# LP_ECG_Main-X01.net
KiCad netlist of a schematic drawn in Altium Designer
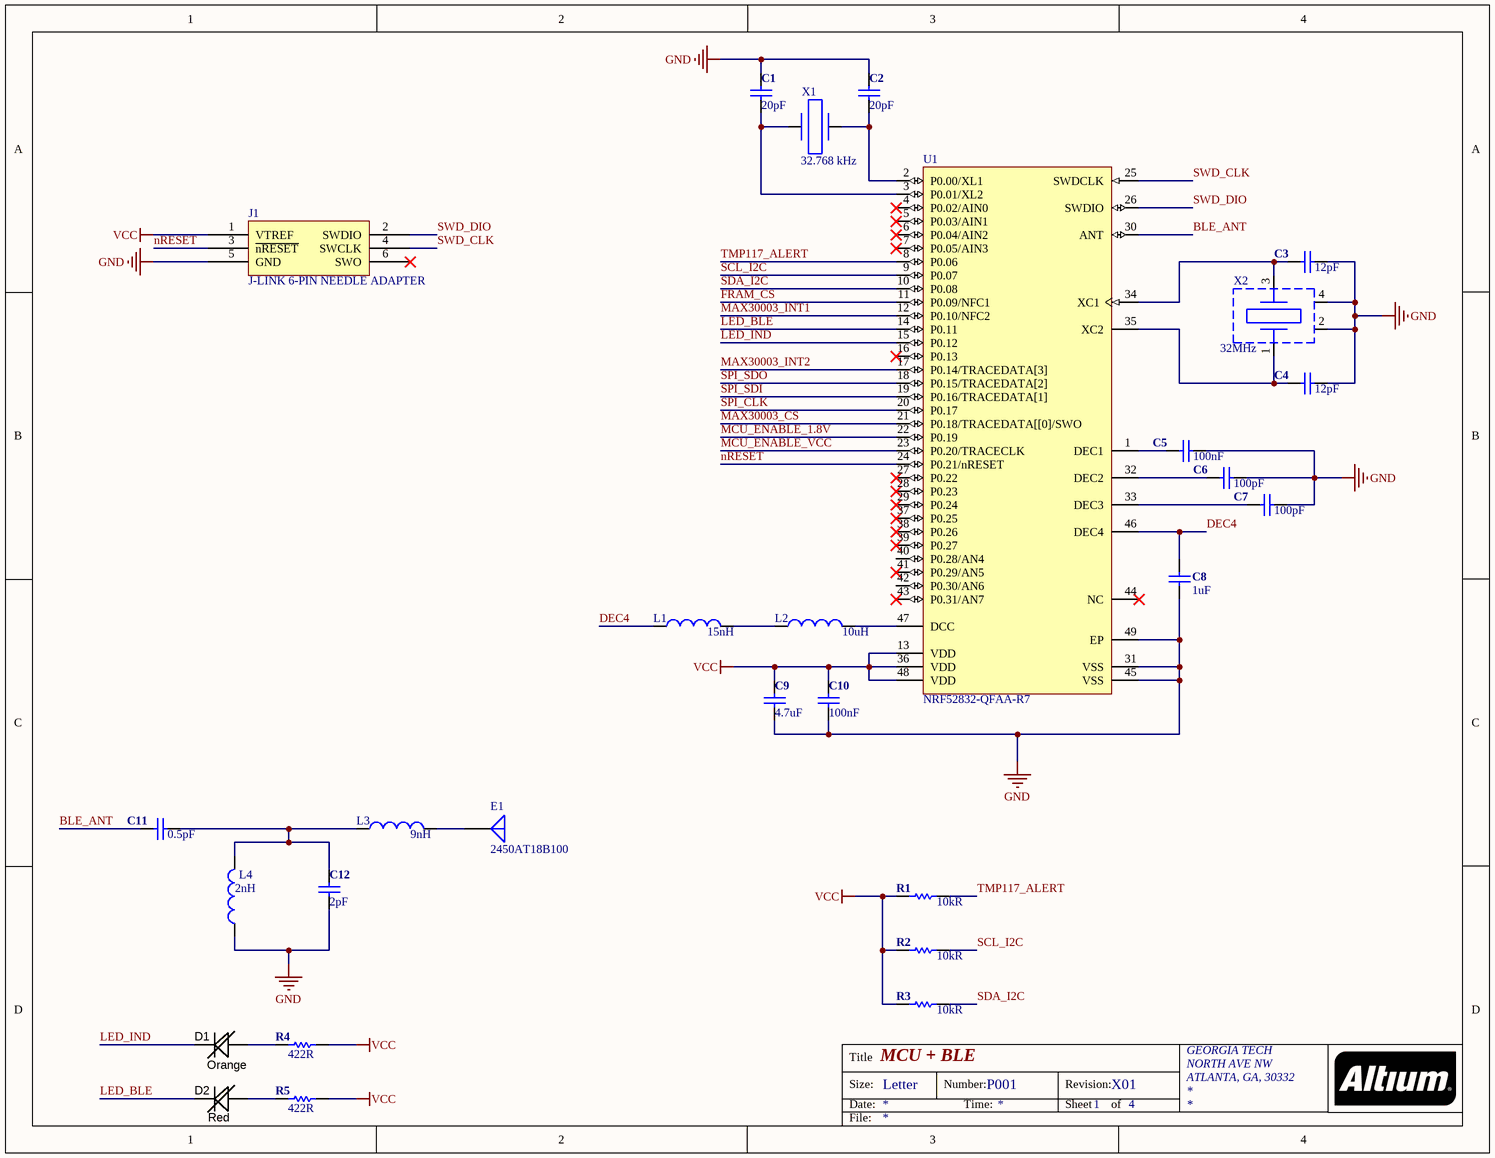
[diagram p0: LP_ECG_Main-X01.SchDoc]

(export (version "E")
  (design (tool "Eeschema 10.0.6"))
  (components
    (comp (ref "C1")
      (value "20pF")
      (footprint "C0402")
      (fields
        (field (name "MANUFACTURER") "Murata")
        (field (name "MANUFACTURER PART NUMBER") "GJM1555C1H200FB01D")
      )
      (libsource (lib "LP_ECG-X01") (part "C-0402(1005)"))
    )
    (comp (ref "C2")
      (value "20pF")
      (footprint "C0402")
      (fields
        (field (name "MANUFACTURER") "Murata")
        (field (name "MANUFACTURER PART NUMBER") "GJM1555C1H200FB01D")
      )
      (libsource (lib "LP_ECG-X01") (part "C-0402(1005)"))
    )
    (comp (ref "C3")
      (value "12pF")
      (footprint "C0402")
      (fields
        (field (name "MANUFACTURER") "Kyocera AVX")
        (field (name "MANUFACTURER PART NUMBER") "04025U120FAT2A")
        (field (name "TOLERANCE") "1%")
      )
      (libsource (lib "LP_ECG-X01") (part "C-0402(1005)"))
    )
    (comp (ref "C4")
      (value "12pF")
      (footprint "C0402")
      (fields
        (field (name "MANUFACTURER") "Kyocera AVX")
        (field (name "MANUFACTURER PART NUMBER") "04025U120FAT2A")
        (field (name "TOLERANCE") "1%")
      )
      (libsource (lib "LP_ECG-X01") (part "C-0402(1005)"))
    )
    (comp (ref "C5")
      (value "100nF")
      (footprint "C0402")
      (fields
        (field (name "MANUFACTURER") "Taiyo Yuden")
        (field (name "MANUFACTURER PART NUMBER") "TMK105BJ104KV-F")
        (field (name "TOLERANCE") "10%")
      )
      (libsource (lib "LP_ECG-X01") (part "C-0402(1005)"))
    )
    (comp (ref "C6")
      (value "100pF")
      (footprint "C0402")
      (fields
        (field (name "MANUFACTURER") "Yageo")
        (field (name "MANUFACTURER PART NUMBER") "CC0402FRNPO9BN101")
        (field (name "TOLERANCE") "1%")
      )
      (libsource (lib "LP_ECG-X01") (part "C-0402(1005)"))
    )
    (comp (ref "C7")
      (value "100pF")
      (footprint "C0402")
      (fields
        (field (name "MANUFACTURER") "Yageo")
        (field (name "MANUFACTURER PART NUMBER") "CC0402FRNPO9BN101")
        (field (name "TOLERANCE") "1%")
      )
      (libsource (lib "LP_ECG-X01") (part "C-0402(1005)"))
    )
    (comp (ref "C8")
      (value "1uF")
      (footprint "C0402")
      (fields
        (field (name "MANUFACTURER") "Yageo")
        (field (name "MANUFACTURER PART NUMBER") "CC0402MRX5R5BB105")
        (field (name "TOLERANCE") "20%")
      )
      (libsource (lib "LP_ECG-X01") (part "C-0402(1005)"))
    )
    (comp (ref "C9")
      (value "4.7uF")
      (footprint "C0402")
      (fields
        (field (name "MANUFACTURER") "Murata")
        (field (name "MANUFACTURER PART NUMBER") "GRM155R60J475ME87J")
      )
      (libsource (lib "LP_ECG-X01") (part "C-0402(1005)"))
    )
    (comp (ref "C10")
      (value "100nF")
      (footprint "C0402")
      (fields
        (field (name "MANUFACTURER") "Taiyo Yuden")
        (field (name "MANUFACTURER PART NUMBER") "TMK105BJ104KV-F")
      )
      (libsource (lib "LP_ECG-X01") (part "C-0402(1005)"))
    )
    (comp (ref "C11")
      (value "0.5pF")
      (footprint "C0402")
      (fields
        (field (name "MANUFACTURER") "Murata")
        (field (name "MANUFACTURER PART NUMBER") "GJM1555C1HR50WB01D")
        (field (name "VOLTAGE") "50V")
      )
      (libsource (lib "LP_ECG-X01") (part "C-0402(1005)"))
    )
    (comp (ref "C12")
      (value "2pF")
      (footprint "C0402")
      (fields
        (field (name "MANUFACTURER") "Murata")
        (field (name "MANUFACTURER PART NUMBER") "GJM1555C1H2R0BB01D")
      )
      (libsource (lib "LP_ECG-X01") (part "C-0402(1005)"))
    )
    (comp (ref "D1")
      (value "Orange")
      (footprint "LED_0402")
      (description "Single Color LED, Super Bright Orange, Water Clear, 0.8mm")
      (fields
        (field (name "MANUFACTURER") "Kingbright")
        (field (name "MANUFACTURER PART NUMBER") "APHHS1005SECK")
      )
      (libsource (lib "LP_ECG-X01") (part "LED_0402(1005)"))
    )
    (comp (ref "D2")
      (value "Red")
      (footprint "LED_0402")
      (description "Single Color LED, Hyper Red, Water Clear, 0.8mm")
      (fields
        (field (name "MANUFACTURER") "Kingbright")
        (field (name "MANUFACTURER PART NUMBER") "APHHS1005SURCK")
      )
      (libsource (lib "LP_ECG-X01") (part "LED_0402(1005)"))
    )
    (comp (ref "E1")
      (value "2450AT18B100")
      (footprint "2450AT18B100")
      (description "RF/Microwave Antenna, 2400MHz Min, 2500MHz Max")
      (fields
        (field (name "MANUFACTURER") "Johanson")
        (field (name "MANUFACTURER PART NUMBER") "2450AT18B100E")
      )
      (libsource (lib "LP_ECG-X01") (part "2450AT18B100"))
    )
    (comp (ref "J1")
      (value "J-LINK 6-PIN NEEDLE ADAPTER")
      (footprint "J-LINK 6 PIN NEEDLE")
      (fields
        (field (name "MANUFACTURER") "Segger")
        (field (name "MANUFACTURER PART NUMBER") "8.06.16 J-LINK 6-PIN NEEDLE ADAPTER")
      )
      (libsource (lib "LP_ECG-X01") (part "J-Link 6 pin needle"))
    )
    (comp (ref "L1")
      (value "15nH")
      (footprint "L0402")
      (description "General Purpose Inductor, 0.015uH, 5%, 1 Element, Ferrite-Core, SMD, 0402")
      (fields
        (field (name "MANUFACTURER") "Taiyo Yuden")
        (field (name "MANUFACTURER PART NUMBER") "HK100515NJ-T")
      )
      (libsource (lib "LP_ECG-X01") (part "I-0402(1005)"))
    )
    (comp (ref "L2")
      (value "10uH")
      (footprint "L0603")
      (description "General Purpose Inductor, 10uH, 10%, 1 Element, Ferrite-Core, SMD, 0603")
      (fields
        (field (name "MANUFACTURER") "Taiyo Yuden")
        (field (name "MANUFACTURER PART NUMBER") "CBMF1608T100K")
      )
      (libsource (lib "LP_ECG-X01") (part "I-0603(1608)"))
    )
    (comp (ref "L3")
      (value "9nH")
      (footprint "L0402")
      (description "General Purpose Inductor, 0.009uH, 2%, 1 Element, SMD")
      (fields
        (field (name "MANUFACTURER") "Murata")
        (field (name "MANUFACTURER PART NUMBER") "LQW15AN9N0G80D")
      )
      (libsource (lib "LP_ECG-X01") (part "I-0402(1005)"))
    )
    (comp (ref "L4")
      (value "2nH")
      (footprint "L0402")
      (description "General Purpose Inductor, 0.002uH, 5%, 1 Element, Ceramic-Core, SMD, 0402")
      (fields
        (field (name "MANUFACTURER") "Abracon")
        (field (name "MANUFACTURER PART NUMBER") "AISC-0402-2N0J-T")
      )
      (libsource (lib "LP_ECG-X01") (part "I-0402(1005)"))
    )
    (comp (ref "R1")
      (value "10kR")
      (footprint "R0402")
      (fields
        (field (name "MANUFACTURER") "Yageo")
        (field (name "MANUFACTURER PART NUMBER") "AC0402FR-0710KL")
        (field (name "TOLERANCE") "1%")
      )
      (libsource (lib "LP_ECG-X01") (part "R-0402(1005)"))
    )
    (comp (ref "R2")
      (value "10kR")
      (footprint "R0402")
      (fields
        (field (name "MANUFACTURER") "Yageo")
        (field (name "MANUFACTURER PART NUMBER") "AC0402FR-0710KL")
        (field (name "TOLERANCE") "1%")
      )
      (libsource (lib "LP_ECG-X01") (part "R-0402(1005)"))
    )
    (comp (ref "R3")
      (value "10kR")
      (footprint "R0402")
      (fields
        (field (name "MANUFACTURER") "Yageo")
        (field (name "MANUFACTURER PART NUMBER") "AC0402FR-0710KL")
        (field (name "TOLERANCE") "1%")
      )
      (libsource (lib "LP_ECG-X01") (part "R-0402(1005)"))
    )
    (comp (ref "R4")
      (value "422R")
      (footprint "R0402")
      (description "Fixed Resistor, Thin Film, 0.0625W, 422ohm, 50V, 0.1% +/-Tol, 25ppm/Cel, Surface Mount, 0402")
      (fields
        (field (name "MANUFACTURER") "Yageo")
        (field (name "MANUFACTURER PART NUMBER") "RT0402BRD07422RL")
      )
      (libsource (lib "LP_ECG-X01") (part "R-0402(1005)"))
    )
    (comp (ref "R5")
      (value "422R")
      (footprint "R0402")
      (description "Fixed Resistor, Thin Film, 0.0625W, 422ohm, 50V, 0.1% +/-Tol, 25ppm/Cel, Surface Mount, 0402")
      (fields
        (field (name "MANUFACTURER") "Yageo")
        (field (name "MANUFACTURER PART NUMBER") "RT0402BRD07422RL")
      )
      (libsource (lib "LP_ECG-X01") (part "R-0402(1005)"))
    )
    (comp (ref "U1")
      (value "NRF52832-QFAA-R7")
      (footprint "NRF52832-QFAA-R7")
      (description "Telecom Circuit, 1-Func")
      (fields
        (field (name "MANUFACTURER") "Nordic Semiconductor")
        (field (name "MANUFACTURER PART NUMBER") "NRF52832-QFAB-R")
      )
      (libsource (lib "LP_ECG-X01") (part "NRSC-NRF52832-QF-48"))
    )
    (comp (ref "X1")
      (value "32.768 kHz")
      (footprint "CRYSTAL_1MM2_X_1MM0")
      (description "Parallel - Fundamental Quartz Crystal, 0.032768MHz Nom")
      (fields
        (field (name "MANUFACTURER") "ECS International")
        (field (name "MANUFACTURER PART NUMBER") "ECS-.327-12.5-1210-TR")
      )
      (libsource (lib "LP_ECG-X01") (part "CRYSTAL_32K768"))
    )
    (comp (ref "X2")
      (value "32MHz")
      (footprint "CRYSTAL_1MM6_X_1MM2")
      (description "Parallel - Fundamental Quartz Crystal, 32MHz Nom")
      (fields (field (name "MANUFACTURER") "Diodes") (field (name "MANUFACTURER PART NUMBER") "US3200005Z"))
      (libsource (lib "LP_ECG-X01") (part "CRYSTAL_32MHz"))
    )
  )
  (nets
    (net (code "1") (name "/BLE_ANT") (class "Default")
      (node (ref "C11") (pin "1") (pinfunction "1_1") (pintype "passive"))
      (node (ref "U1") (pin "30") (pinfunction "ANT_30") (pintype "bidirectional"))
    )
    (net (code "2") (name "/DEC4") (class "Default")
      (node (ref "C8") (pin "2") (pinfunction "2_2") (pintype "passive"))
      (node (ref "L1") (pin "1") (pinfunction "1_1") (pintype "passive"))
      (node (ref "U1") (pin "46") (pinfunction "DEC4_46") (pintype "passive"))
    )
    (net (code "3") (name "/FRAM_CS") (class "Default")
      (node (ref "U1") (pin "11") (pinfunction "P0.09/NFC1_11") (pintype "bidirectional"))
    )
    (net (code "4") (name "/LED_BLE") (class "Default")
      (node (ref "D2") (pin "K") (pinfunction "K_K") (pintype "passive"))
      (node (ref "U1") (pin "14") (pinfunction "P0.11_14") (pintype "bidirectional"))
    )
    (net (code "5") (name "/LED_IND") (class "Default")
      (node (ref "D1") (pin "K") (pinfunction "K_K") (pintype "passive"))
      (node (ref "U1") (pin "15") (pinfunction "P0.12_15") (pintype "bidirectional"))
    )
    (net (code "6") (name "/MAX30003_CS") (class "Default")
      (node (ref "U1") (pin "21") (pinfunction "P0.18/TRACEDATA[[0]/SWO_21") (pintype "bidirectional"))
    )
    (net (code "7") (name "/MAX30003_INT1") (class "Default")
      (node (ref "U1") (pin "12") (pinfunction "P0.10/NFC2_12") (pintype "bidirectional"))
    )
    (net (code "8") (name "/MAX30003_INT2") (class "Default")
      (node (ref "U1") (pin "17") (pinfunction "P0.14/TRACEDATA[3]_17") (pintype "bidirectional"))
    )
    (net (code "9") (name "/MCU_ENABLE_1.8V") (class "Default")
      (node (ref "U1") (pin "22") (pinfunction "P0.19_22") (pintype "bidirectional"))
    )
    (net (code "10") (name "/MCU_ENABLE_VCC") (class "Default")
      (node (ref "U1") (pin "23") (pinfunction "P0.20/TRACECLK_23") (pintype "bidirectional"))
    )
    (net (code "11") (name "/SCL_I2C") (class "Default")
      (node (ref "R2") (pin "2") (pinfunction "2_2") (pintype "passive"))
      (node (ref "U1") (pin "9") (pinfunction "P0.07_9") (pintype "bidirectional"))
    )
    (net (code "12") (name "/SDA_I2C") (class "Default")
      (node (ref "R3") (pin "2") (pinfunction "2_2") (pintype "passive"))
      (node (ref "U1") (pin "10") (pinfunction "P0.08_10") (pintype "bidirectional"))
    )
    (net (code "13") (name "/SPI_CLK") (class "Default")
      (node (ref "U1") (pin "20") (pinfunction "P0.17_20") (pintype "bidirectional"))
    )
    (net (code "14") (name "/SPI_SDI") (class "Default")
      (node (ref "U1") (pin "19") (pinfunction "P0.16/TRACEDATA[1]_19") (pintype "bidirectional"))
    )
    (net (code "15") (name "/SPI_SDO") (class "Default")
      (node (ref "U1") (pin "18") (pinfunction "P0.15/TRACEDATA[2]_18") (pintype "bidirectional"))
    )
    (net (code "16") (name "/SWD_CLK") (class "Default")
      (node (ref "J1") (pin "4") (pinfunction "SWCLK_4") (pintype "passive"))
      (node (ref "U1") (pin "25") (pinfunction "SWDCLK_25") (pintype "input"))
    )
    (net (code "17") (name "/SWD_DIO") (class "Default")
      (node (ref "J1") (pin "2") (pinfunction "SWDIO_2") (pintype "passive"))
      (node (ref "U1") (pin "26") (pinfunction "SWDIO_26") (pintype "bidirectional"))
    )
    (net (code "18") (name "/TMP117_ALERT") (class "Default")
      (node (ref "R1") (pin "2") (pinfunction "2_2") (pintype "passive"))
      (node (ref "U1") (pin "8") (pinfunction "P0.06_8") (pintype "bidirectional"))
    )
    (net (code "19") (name "/nRESET") (class "Default")
      (node (ref "J1") (pin "3") (pinfunction "~{nRESET}_3") (pintype "passive"))
      (node (ref "U1") (pin "24") (pinfunction "P0.21/nRESET_24") (pintype "bidirectional"))
    )
    (net (code "20") (name "GND") (class "Default")
      (node (ref "C1") (pin "1") (pinfunction "1_1") (pintype "passive"))
      (node (ref "C10") (pin "2") (pinfunction "2_2") (pintype "passive"))
      (node (ref "C12") (pin "2") (pinfunction "2_2") (pintype "passive"))
      (node (ref "C2") (pin "1") (pinfunction "1_1") (pintype "passive"))
      (node (ref "C3") (pin "2") (pinfunction "2_2") (pintype "passive"))
      (node (ref "C4") (pin "2") (pinfunction "2_2") (pintype "passive"))
      (node (ref "C5") (pin "2") (pinfunction "2_2") (pintype "passive"))
      (node (ref "C6") (pin "2") (pinfunction "2_2") (pintype "passive"))
      (node (ref "C7") (pin "2") (pinfunction "2_2") (pintype "passive"))
      (node (ref "C8") (pin "1") (pinfunction "1_1") (pintype "passive"))
      (node (ref "C9") (pin "2") (pinfunction "2_2") (pintype "passive"))
      (node (ref "J1") (pin "5") (pinfunction "GND_5") (pintype "passive"))
      (node (ref "L4") (pin "1") (pinfunction "1_1") (pintype "passive"))
      (node (ref "U1") (pin "31") (pinfunction "VSS_31") (pintype "power_in"))
      (node (ref "U1") (pin "45") (pinfunction "VSS_45") (pintype "power_in"))
      (node (ref "U1") (pin "49") (pinfunction "EP_49") (pintype "power_in"))
      (node (ref "X2") (pin "2") (pinfunction "GND_2") (pintype "passive"))
      (node (ref "X2") (pin "4") (pinfunction "GND_4") (pintype "passive"))
    )
    (net (code "21") (name "Net-(C11-Pad2)") (class "Default")
      (node (ref "C11") (pin "2") (pinfunction "2_2") (pintype "passive"))
      (node (ref "C12") (pin "1") (pinfunction "1_1") (pintype "passive"))
      (node (ref "L3") (pin "1") (pinfunction "1_1") (pintype "passive"))
      (node (ref "L4") (pin "2") (pinfunction "2_2") (pintype "passive"))
    )
    (net (code "22") (name "Net-(D1-PadA)") (class "Default")
      (node (ref "D1") (pin "A") (pinfunction "A_A") (pintype "passive"))
      (node (ref "R4") (pin "2") (pinfunction "2_2") (pintype "passive"))
    )
    (net (code "23") (name "Net-(D2-PadA)") (class "Default")
      (node (ref "D2") (pin "A") (pinfunction "A_A") (pintype "passive"))
      (node (ref "R5") (pin "2") (pinfunction "2_2") (pintype "passive"))
    )
    (net (code "24") (name "Net-(E1-A)") (class "Default")
      (node (ref "E1") (pin "1") (pinfunction "A_1") (pintype "passive"))
      (node (ref "L3") (pin "2") (pinfunction "2_2") (pintype "passive"))
    )
    (net (code "25") (name "Net-(L1-Pad2)") (class "Default")
      (node (ref "L1") (pin "2") (pinfunction "2_2") (pintype "passive"))
      (node (ref "L2") (pin "1") (pinfunction "1_1") (pintype "passive"))
    )
    (net (code "26") (name "Net-(U1-DCC)") (class "Default")
      (node (ref "L2") (pin "2") (pinfunction "2_2") (pintype "passive"))
      (node (ref "U1") (pin "47") (pinfunction "DCC_47") (pintype "power_in"))
    )
    (net (code "27") (name "Net-(U1-DEC1)") (class "Default")
      (node (ref "C5") (pin "1") (pinfunction "1_1") (pintype "passive"))
      (node (ref "U1") (pin "1") (pinfunction "DEC1_1") (pintype "passive"))
    )
    (net (code "28") (name "Net-(U1-DEC2)") (class "Default")
      (node (ref "C6") (pin "1") (pinfunction "1_1") (pintype "passive"))
      (node (ref "U1") (pin "32") (pinfunction "DEC2_32") (pintype "passive"))
    )
    (net (code "29") (name "Net-(U1-DEC3)") (class "Default")
      (node (ref "C7") (pin "1") (pinfunction "1_1") (pintype "passive"))
      (node (ref "U1") (pin "33") (pinfunction "DEC3_33") (pintype "passive"))
    )
    (net (code "30") (name "Net-(U1-P0.00{slash}XL1)") (class "Default")
      (node (ref "C2") (pin "2") (pinfunction "2_2") (pintype "passive"))
      (node (ref "U1") (pin "2") (pinfunction "P0.00/XL1_2") (pintype "bidirectional"))
      (node (ref "X1") (pin "2") (pinfunction "2_2") (pintype "passive"))
    )
    (net (code "31") (name "Net-(U1-P0.01{slash}XL2)") (class "Default")
      (node (ref "C1") (pin "2") (pinfunction "2_2") (pintype "passive"))
      (node (ref "U1") (pin "3") (pinfunction "P0.01/XL2_3") (pintype "bidirectional"))
      (node (ref "X1") (pin "1") (pinfunction "1_1") (pintype "passive"))
    )
    (net (code "32") (name "Net-(U1-XC1)") (class "Default")
      (node (ref "C3") (pin "1") (pinfunction "1_1") (pintype "passive"))
      (node (ref "U1") (pin "34") (pinfunction "XC1_34") (pintype "input"))
      (node (ref "X2") (pin "3") (pinfunction "3_3") (pintype "passive"))
    )
    (net (code "33") (name "Net-(U1-XC2)") (class "Default")
      (node (ref "C4") (pin "1") (pinfunction "1_1") (pintype "passive"))
      (node (ref "U1") (pin "35") (pinfunction "XC2_35") (pintype "passive"))
      (node (ref "X2") (pin "1") (pinfunction "1_1") (pintype "passive"))
    )
    (net (code "34") (name "VCC") (class "Default")
      (node (ref "C10") (pin "1") (pinfunction "1_1") (pintype "passive"))
      (node (ref "C9") (pin "1") (pinfunction "1_1") (pintype "passive"))
      (node (ref "J1") (pin "1") (pinfunction "VTREF_1") (pintype "passive"))
      (node (ref "R1") (pin "1") (pinfunction "1_1") (pintype "passive"))
      (node (ref "R2") (pin "1") (pinfunction "1_1") (pintype "passive"))
      (node (ref "R3") (pin "1") (pinfunction "1_1") (pintype "passive"))
      (node (ref "R4") (pin "1") (pinfunction "1_1") (pintype "passive"))
      (node (ref "R5") (pin "1") (pinfunction "1_1") (pintype "passive"))
      (node (ref "U1") (pin "13") (pinfunction "VDD_13") (pintype "power_in"))
      (node (ref "U1") (pin "36") (pinfunction "VDD_36") (pintype "power_in"))
      (node (ref "U1") (pin "48") (pinfunction "VDD_48") (pintype "power_in"))
    )
    (net (code "35") (name "unconnected-(J1-SWO-Pad6)") (class "Default")
      (node (ref "J1") (pin "6") (pinfunction "SWO_6") (pintype "passive+no_connect"))
    )
    (net (code "36") (name "unconnected-(U1-NC-Pad44)") (class "Default")
      (node (ref "U1") (pin "44") (pinfunction "NC_44") (pintype "passive+no_connect"))
    )
    (net (code "37") (name "unconnected-(U1-P0.02{slash}AIN0-Pad4)") (class "Default")
      (node (ref "U1") (pin "4") (pinfunction "P0.02/AIN0_4") (pintype "bidirectional+no_connect"))
    )
    (net (code "38") (name "unconnected-(U1-P0.03{slash}AIN1-Pad5)") (class "Default")
      (node (ref "U1") (pin "5") (pinfunction "P0.03/AIN1_5") (pintype "bidirectional+no_connect"))
    )
    (net (code "39") (name "unconnected-(U1-P0.04{slash}AIN2-Pad6)") (class "Default")
      (node (ref "U1") (pin "6") (pinfunction "P0.04/AIN2_6") (pintype "bidirectional+no_connect"))
    )
    (net (code "40") (name "unconnected-(U1-P0.05{slash}AIN3-Pad7)") (class "Default")
      (node (ref "U1") (pin "7") (pinfunction "P0.05/AIN3_7") (pintype "bidirectional+no_connect"))
    )
    (net (code "41") (name "unconnected-(U1-P0.13-Pad16)") (class "Default")
      (node (ref "U1") (pin "16") (pinfunction "P0.13_16") (pintype "bidirectional+no_connect"))
    )
    (net (code "42") (name "unconnected-(U1-P0.22-Pad27)") (class "Default")
      (node (ref "U1") (pin "27") (pinfunction "P0.22_27") (pintype "bidirectional+no_connect"))
    )
    (net (code "43") (name "unconnected-(U1-P0.23-Pad28)") (class "Default")
      (node (ref "U1") (pin "28") (pinfunction "P0.23_28") (pintype "bidirectional+no_connect"))
    )
    (net (code "44") (name "unconnected-(U1-P0.24-Pad29)") (class "Default")
      (node (ref "U1") (pin "29") (pinfunction "P0.24_29") (pintype "bidirectional+no_connect"))
    )
    (net (code "45") (name "unconnected-(U1-P0.25-Pad37)") (class "Default")
      (node (ref "U1") (pin "37") (pinfunction "P0.25_37") (pintype "bidirectional+no_connect"))
    )
    (net (code "46") (name "unconnected-(U1-P0.26-Pad38)") (class "Default")
      (node (ref "U1") (pin "38") (pinfunction "P0.26_38") (pintype "bidirectional+no_connect"))
    )
    (net (code "47") (name "unconnected-(U1-P0.27-Pad39)") (class "Default")
      (node (ref "U1") (pin "39") (pinfunction "P0.27_39") (pintype "bidirectional+no_connect"))
    )
    (net (code "48") (name "unconnected-(U1-P0.28{slash}AN4-Pad40)") (class "Default")
      (node (ref "U1") (pin "40") (pinfunction "P0.28/AN4_40") (pintype "bidirectional"))
    )
    (net (code "49") (name "unconnected-(U1-P0.29{slash}AN5-Pad41)") (class "Default")
      (node (ref "U1") (pin "41") (pinfunction "P0.29/AN5_41") (pintype "bidirectional+no_connect"))
    )
    (net (code "50") (name "unconnected-(U1-P0.30{slash}AN6-Pad42)") (class "Default")
      (node (ref "U1") (pin "42") (pinfunction "P0.30/AN6_42") (pintype "bidirectional"))
    )
    (net (code "51") (name "unconnected-(U1-P0.31{slash}AN7-Pad43)") (class "Default")
      (node (ref "U1") (pin "43") (pinfunction "P0.31/AN7_43") (pintype "bidirectional+no_connect"))
    )
  )
)
